# MCU.net
KiCad netlist of a schematic drawn in Altium Designer
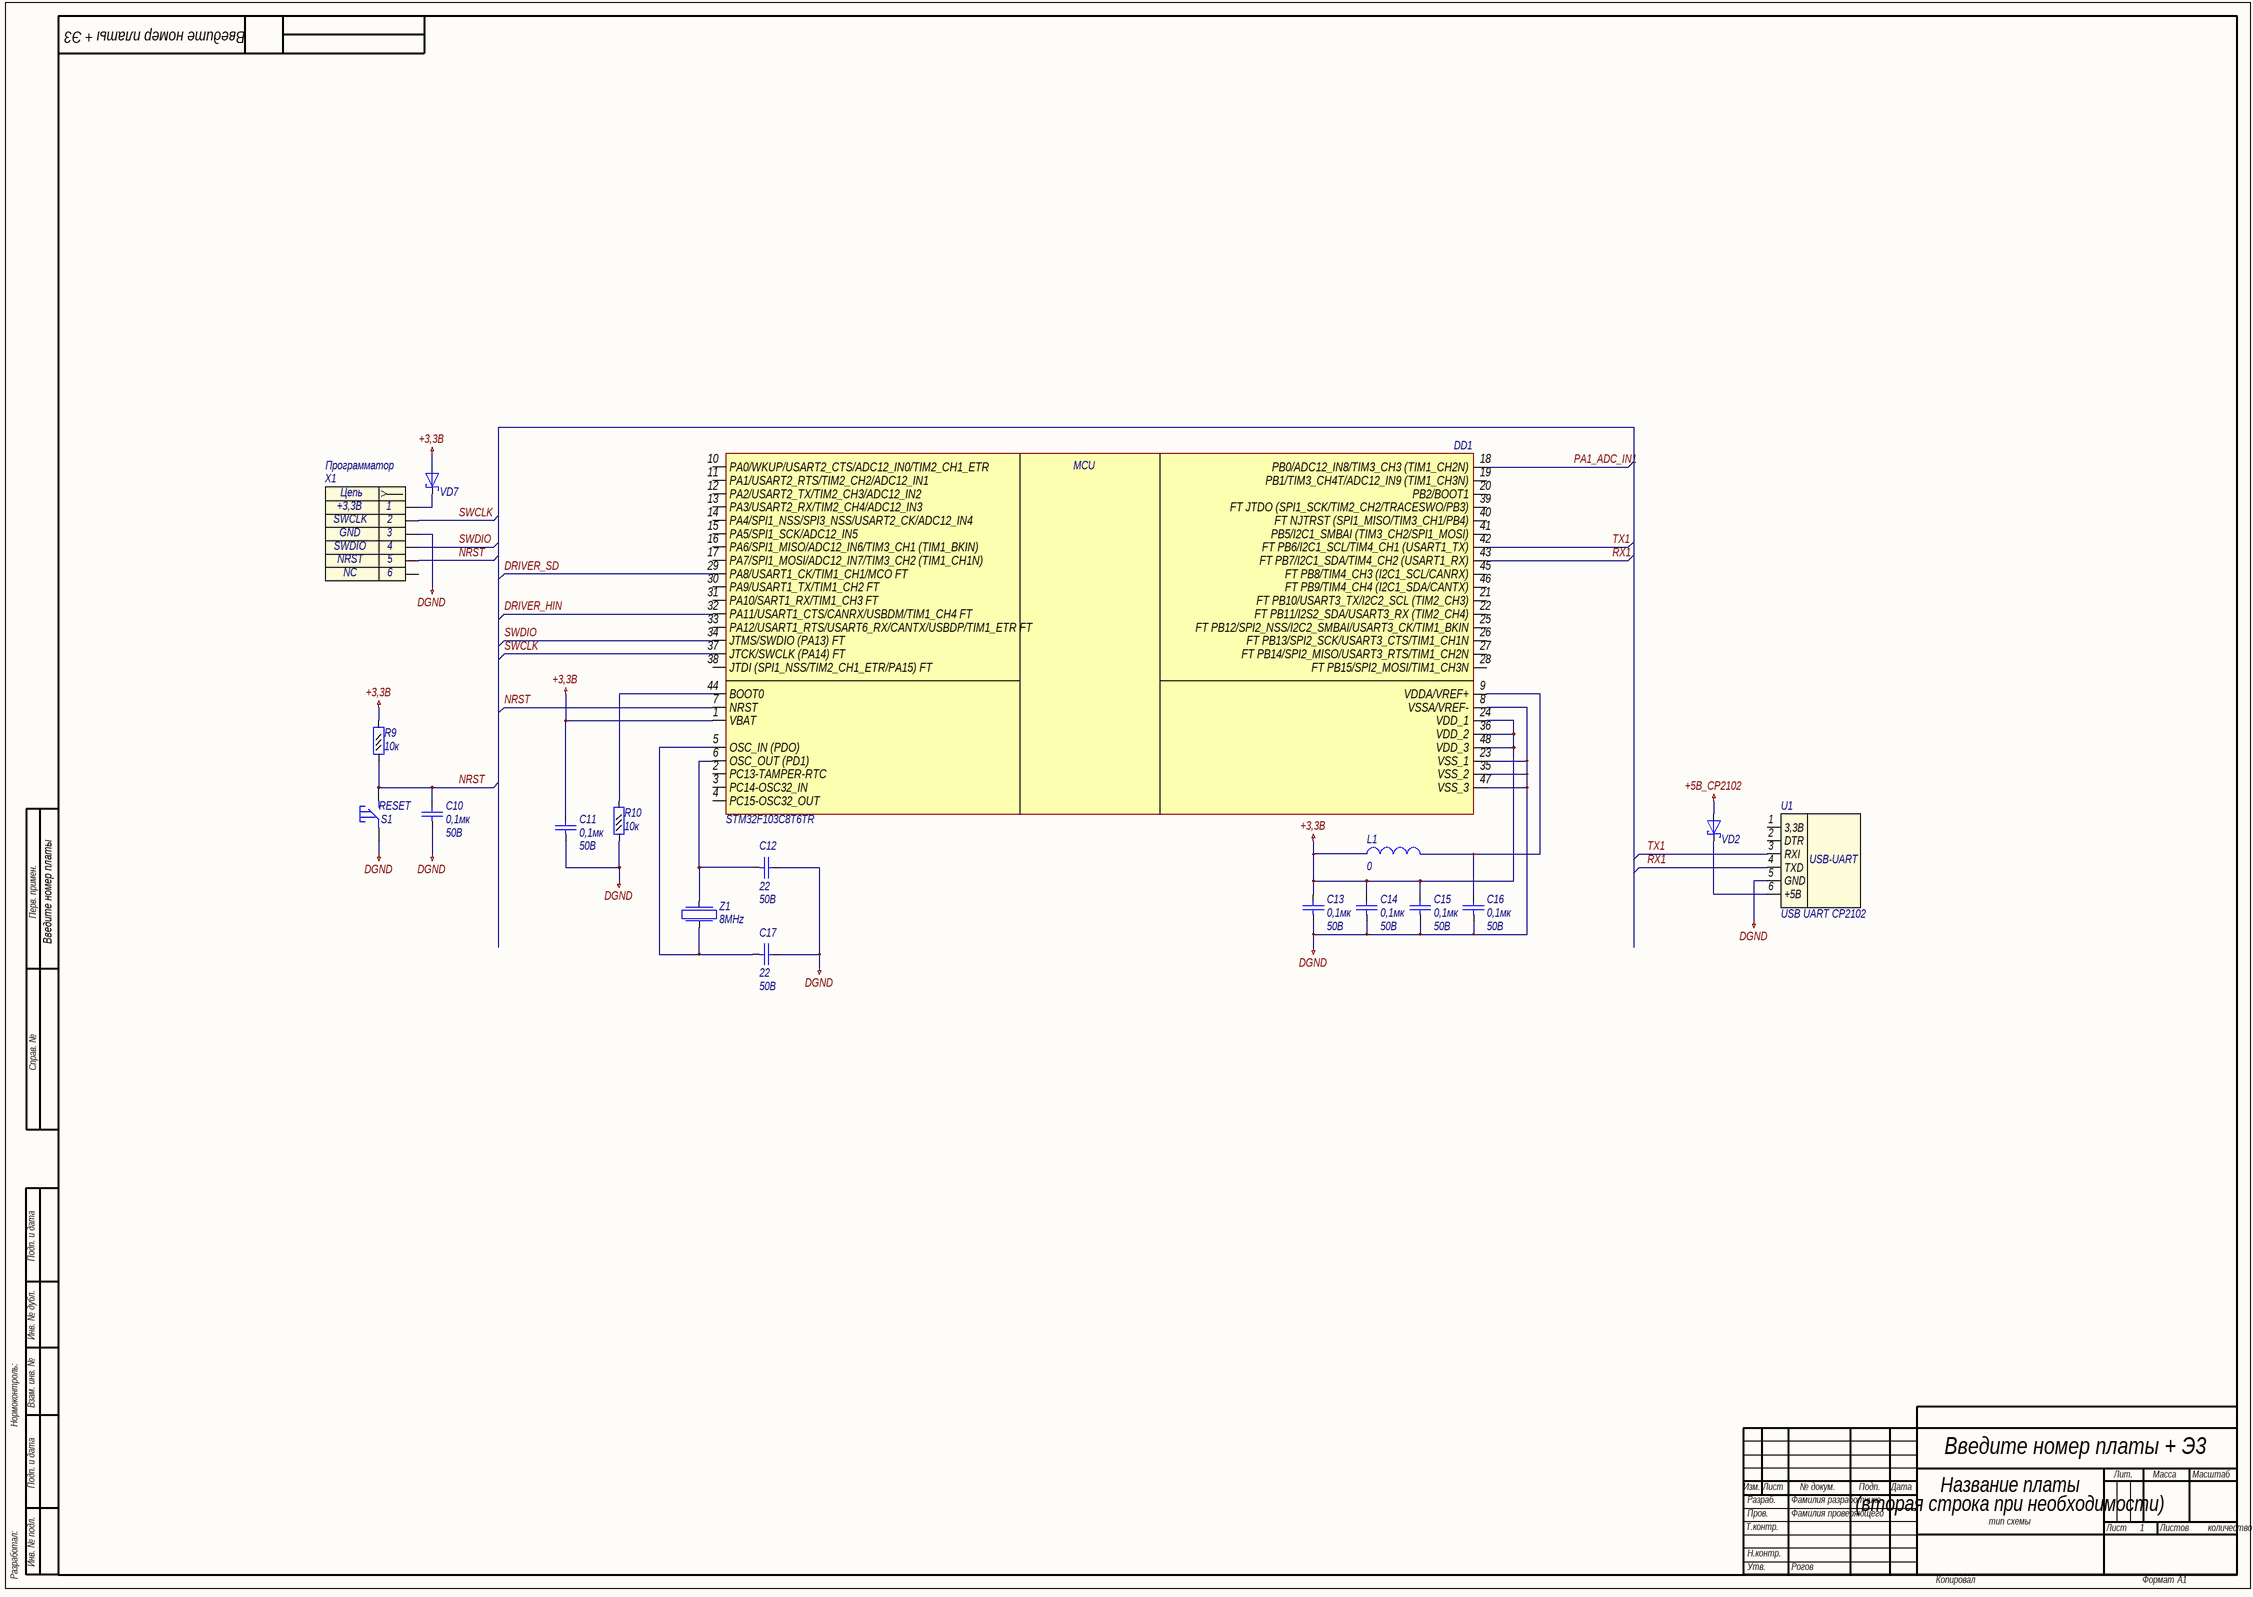
[diagram p0: MCU.SchDoc]

(export (version "E")
  (design (tool "Eeschema 10.0.6"))
  (components
    (comp (ref "C10")
      (value "0,1мк")
      (footprint "C0603")
      (description "Конденсатор")
      (fields
        (field (name "VOLTAGE") "50B")
        (field (name "PART NUMBER") "GRM188R71H104KA93D")
        (field (name "Comment") "Capacitor")
      )
      (libsource (lib "MOP44") (part "Capacitor"))
    )
    (comp (ref "C11")
      (value "0,1мк")
      (footprint "C0603")
      (description "Конденсатор")
      (fields
        (field (name "VOLTAGE") "50B")
        (field (name "PART NUMBER") "GRM188R71H104KA93D")
        (field (name "Comment") "Capacitor")
      )
      (libsource (lib "MOP44") (part "Capacitor"))
    )
    (comp (ref "C12")
      (value "22")
      (footprint "C0603")
      (description "Конденсатор")
      (fields
        (field (name "VOLTAGE") "50B")
        (field (name "PART NUMBER") "CC0603JRNPO9BN220")
        (field (name "Comment") "Capacitor")
      )
      (libsource (lib "MOP44") (part "Capacitor"))
    )
    (comp (ref "C13")
      (value "0,1мк")
      (footprint "C0603")
      (description "Конденсатор")
      (fields
        (field (name "VOLTAGE") "50B")
        (field (name "PART NUMBER") "GRM188R71H104KA93D")
        (field (name "Comment") "Capacitor")
      )
      (libsource (lib "MOP44") (part "Capacitor"))
    )
    (comp (ref "C14")
      (value "0,1мк")
      (footprint "C0603")
      (description "Конденсатор")
      (fields
        (field (name "VOLTAGE") "50B")
        (field (name "PART NUMBER") "GRM188R71H104KA93D")
        (field (name "Comment") "Capacitor")
      )
      (libsource (lib "MOP44") (part "Capacitor"))
    )
    (comp (ref "C15")
      (value "0,1мк")
      (footprint "C0603")
      (description "Конденсатор")
      (fields
        (field (name "VOLTAGE") "50B")
        (field (name "PART NUMBER") "GRM188R71H104KA93D")
        (field (name "Comment") "Capacitor")
      )
      (libsource (lib "MOP44") (part "Capacitor"))
    )
    (comp (ref "C16")
      (value "0,1мк")
      (footprint "C0603")
      (description "Конденсатор")
      (fields
        (field (name "VOLTAGE") "50B")
        (field (name "PART NUMBER") "GRM188R71H104KA93D")
        (field (name "Comment") "Capacitor")
      )
      (libsource (lib "MOP44") (part "Capacitor"))
    )
    (comp (ref "C17")
      (value "22")
      (footprint "C0603")
      (description "Конденсатор")
      (fields
        (field (name "VOLTAGE") "50B")
        (field (name "PART NUMBER") "CC0603JRNPO9BN220")
        (field (name "Comment") "Capacitor")
      )
      (libsource (lib "MOP44") (part "Capacitor"))
    )
    (comp (ref "DD1")
      (value "STM32F103C8T6TR")
      (footprint "LQFP48")
      (fields (field (name "PART NUMBER") "STM32F103C8T6TR"))
      (libsource (lib "MOP44") (part "STM32F103C8T6TR"))
    )
    (comp (ref "L1")
      (value "0")
      (footprint "L0603")
      (description "EMI Suppression Filter")
      (fields (field (name "PART NUMBER") "BLM18PG181SN1D") (field (name "Comment") "Inductor"))
      (libsource (lib "MOP44") (part "Inductor"))
    )
    (comp (ref "R9")
      (value "10к")
      (footprint "R0603")
      (description "Резистор")
      (fields (field (name "PART NUMBER") "RC0603FR-0710KL") (field (name "POWER") "0,062Вт"))
      (libsource (lib "MOP44") (part "Resistor_0,062Вт"))
    )
    (comp (ref "R10")
      (value "10к")
      (footprint "R0603")
      (description "Резистор")
      (fields (field (name "PART NUMBER") "RC0603FR-0710KL") (field (name "POWER") "0,062Вт"))
      (libsource (lib "MOP44") (part "Resistor_0,062Вт"))
    )
    (comp (ref "S1")
      (value "RESET")
      (footprint "Button_SMD")
      (description "Кнопка")
      (libsource (lib "MOP44") (part "Button"))
    )
    (comp (ref "U1")
      (value "USB UART")
      (footprint "USB UART CP2102")
      (description "USB UART module cp2102")
      (fields (field (name "PART NAME") "USB UART CP2102"))
      (libsource (lib "MOP44") (part "USB UART"))
    )
    (comp (ref "VD2")
      (value "DiodeSchottky")
      (footprint "SOD-523")
      (description "Диод Шоттки")
      (fields (field (name "PART NUMBER") "PMEG2010AEB.115"))
      (libsource (lib "MOP44") (part "DiodeSchottky"))
    )
    (comp (ref "VD7")
      (value "DiodeSchottky")
      (footprint "SOD-523")
      (description "Диод Шоттки")
      (fields (field (name "PART NUMBER") "PMEG2010AEB.115"))
      (libsource (lib "MOP44") (part "DiodeSchottky"))
    )
    (comp (ref "X1")
      (value "Программатор")
      (footprint "PLS2-6")
      (description "Разъем - 6 конт. розетка")
      (libsource (lib "MOP44") (part "Header_6_sct"))
    )
    (comp (ref "Z1")
      (value "Crystal")
      (footprint "HC-49S")
      (description "Кварцевый резонатор")
      (fields (field (name "FREQUENCE") "8MHz") (field (name "PART NUMBER") "8.000MHzHC-49US"))
      (libsource (lib "MOP44") (part "Crystal"))
    )
  )
  (nets
    (net (code "1") (name "+3,3В") (class "Default")
      (node (ref "C11") (pin "2") (pinfunction "2_2") (pintype "passive"))
      (node (ref "C13") (pin "2") (pinfunction "2_2") (pintype "passive"))
      (node (ref "C14") (pin "2") (pinfunction "2_2") (pintype "passive"))
      (node (ref "C15") (pin "2") (pinfunction "2_2") (pintype "passive"))
      (node (ref "DD1") (pin "1") (pinfunction "VBAT_1") (pintype "passive"))
      (node (ref "DD1") (pin "24") (pinfunction "VDD_1_24") (pintype "passive"))
      (node (ref "DD1") (pin "36") (pinfunction "VDD_2_36") (pintype "passive"))
      (node (ref "DD1") (pin "48") (pinfunction "VDD_3_48") (pintype "passive"))
      (node (ref "L1") (pin "1") (pinfunction "1_1") (pintype "passive"))
      (node (ref "R9") (pin "2") (pinfunction "2_2") (pintype "passive"))
      (node (ref "VD7") (pin "2") (pinfunction "A_2") (pintype "passive"))
    )
    (net (code "2") (name "+5B_CP2102") (class "Default")
      (node (ref "VD2") (pin "2") (pinfunction "A_2") (pintype "passive"))
    )
    (net (code "3") (name "/DRIVER_HIN") (class "Default")
      (node (ref "DD1") (pin "32") (pinfunction "PA11/USART1_CTS/CANRX/USBDM/TIM1_CH4_FT_32") (pintype "passive"))
    )
    (net (code "4") (name "/DRIVER_SD") (class "Default")
      (node (ref "DD1") (pin "29") (pinfunction "PA8/USART1_CK/TIM1_CH1/MCO_FT_29") (pintype "passive"))
    )
    (net (code "5") (name "/NRST") (class "Default")
      (node (ref "C10") (pin "2") (pinfunction "2_2") (pintype "passive"))
      (node (ref "DD1") (pin "7") (pinfunction "NRST_7") (pintype "passive"))
      (node (ref "R9") (pin "1") (pinfunction "1_1") (pintype "passive"))
      (node (ref "S1") (pin "4") (pinfunction "4_4") (pintype "passive"))
      (node (ref "X1") (pin "5") (pinfunction "5_5") (pintype "passive"))
    )
    (net (code "6") (name "/PA1_ADC_IN1") (class "Default")
      (node (ref "DD1") (pin "18") (pinfunction "PB0/ADC12_IN8/TIM3_CH3_(TIM1_CH2N)_18") (pintype "passive"))
    )
    (net (code "7") (name "/RX1") (class "Default")
      (node (ref "DD1") (pin "43") (pinfunction "FT_PB7/I2C1_SDA/TIM4_CH2_(USART1_RX)_43") (pintype "passive"))
      (node (ref "U1") (pin "4") (pinfunction "TXD_4") (pintype "power_in"))
    )
    (net (code "8") (name "/SWCLK") (class "Default")
      (node (ref "DD1") (pin "37") (pinfunction "JTCK/SWCLK_(PA14)_FT_37") (pintype "passive"))
      (node (ref "X1") (pin "2") (pinfunction "2_2") (pintype "passive"))
    )
    (net (code "9") (name "/SWDIO") (class "Default")
      (node (ref "DD1") (pin "34") (pinfunction "JTMS/SWDIO_(PA13)_FT_34") (pintype "passive"))
      (node (ref "X1") (pin "4") (pinfunction "4_4") (pintype "passive"))
    )
    (net (code "10") (name "/TX1") (class "Default")
      (node (ref "DD1") (pin "42") (pinfunction "FT_PB6/I2C1_SCL/TIM4_CH1_(USART1_TX)_42") (pintype "passive"))
      (node (ref "U1") (pin "3") (pinfunction "RXI_3") (pintype "power_in"))
    )
    (net (code "11") (name "DGND") (class "Default")
      (node (ref "C10") (pin "1") (pinfunction "1_1") (pintype "passive"))
      (node (ref "C11") (pin "1") (pinfunction "1_1") (pintype "passive"))
      (node (ref "C12") (pin "2") (pinfunction "2_2") (pintype "passive"))
      (node (ref "C13") (pin "1") (pinfunction "1_1") (pintype "passive"))
      (node (ref "C14") (pin "1") (pinfunction "1_1") (pintype "passive"))
      (node (ref "C15") (pin "1") (pinfunction "1_1") (pintype "passive"))
      (node (ref "C16") (pin "1") (pinfunction "1_1") (pintype "passive"))
      (node (ref "C17") (pin "2") (pinfunction "2_2") (pintype "passive"))
      (node (ref "DD1") (pin "23") (pinfunction "VSS_1_23") (pintype "passive"))
      (node (ref "DD1") (pin "35") (pinfunction "VSS_2_35") (pintype "passive"))
      (node (ref "DD1") (pin "47") (pinfunction "VSS_3_47") (pintype "passive"))
      (node (ref "DD1") (pin "8") (pinfunction "VSSA/VREF-_8") (pintype "passive"))
      (node (ref "R10") (pin "1") (pinfunction "1_1") (pintype "passive"))
      (node (ref "S1") (pin "1") (pinfunction "1_1") (pintype "passive"))
      (node (ref "U1") (pin "5") (pinfunction "GND_5") (pintype "power_in"))
      (node (ref "X1") (pin "3") (pinfunction "3_3") (pintype "passive"))
    )
    (net (code "12") (name "Net-(DD1-BOOT0)") (class "Default")
      (node (ref "DD1") (pin "44") (pinfunction "BOOT0_44") (pintype "passive"))
      (node (ref "R10") (pin "2") (pinfunction "2_2") (pintype "passive"))
    )
    (net (code "13") (name "Net-(DD1-OSC_IN_(PDO))") (class "Default")
      (node (ref "C17") (pin "1") (pinfunction "1_1") (pintype "passive"))
      (node (ref "DD1") (pin "5") (pinfunction "OSC_IN_(PDO)_5") (pintype "passive"))
      (node (ref "Z1") (pin "1") (pinfunction "1_1") (pintype "passive"))
    )
    (net (code "14") (name "Net-(DD1-OSC_OUT_(PD1))") (class "Default")
      (node (ref "C12") (pin "1") (pinfunction "1_1") (pintype "passive"))
      (node (ref "DD1") (pin "6") (pinfunction "OSC_OUT_(PD1)_6") (pintype "passive"))
      (node (ref "Z1") (pin "2") (pinfunction "2_2") (pintype "passive"))
    )
    (net (code "15") (name "Net-(DD1-VDDA{slash}VREF+)") (class "Default")
      (node (ref "C16") (pin "2") (pinfunction "2_2") (pintype "passive"))
      (node (ref "DD1") (pin "9") (pinfunction "VDDA/VREF+_9") (pintype "passive"))
      (node (ref "L1") (pin "2") (pinfunction "2_2") (pintype "passive"))
    )
    (net (code "16") (name "Net-(U1-+5B)") (class "Default")
      (node (ref "U1") (pin "6") (pinfunction "+5B_6") (pintype "power_in"))
      (node (ref "VD2") (pin "1") (pinfunction "K_1") (pintype "passive"))
    )
    (net (code "17") (name "Net-(VD7-K)") (class "Default")
      (node (ref "VD7") (pin "1") (pinfunction "K_1") (pintype "passive"))
      (node (ref "X1") (pin "1") (pinfunction "1_1") (pintype "passive"))
    )
    (net (code "18") (name "unconnected-(DD1-FT_JTDO_(SPI1_SCK{slash}TIM2_CH2{slash}TRACESWO{slash}PB3)-Pad39)") (class "Default")
      (node (ref "DD1") (pin "39") (pinfunction "FT_JTDO_(SPI1_SCK/TIM2_CH2/TRACESWO/PB3)_39") (pintype "passive"))
    )
    (net (code "19") (name "unconnected-(DD1-FT_NJTRST_(SPI1_MISO{slash}TIM3_CH1{slash}PB4)-Pad40)") (class "Default")
      (node (ref "DD1") (pin "40") (pinfunction "FT_NJTRST_(SPI1_MISO/TIM3_CH1/PB4)_40") (pintype "passive"))
    )
    (net (code "20") (name "unconnected-(DD1-FT_PB8{slash}TIM4_CH3_(I2C1_SCL{slash}CANRX)-Pad45)") (class "Default")
      (node (ref "DD1") (pin "45") (pinfunction "FT_PB8/TIM4_CH3_(I2C1_SCL/CANRX)_45") (pintype "passive"))
    )
    (net (code "21") (name "unconnected-(DD1-FT_PB9{slash}TIM4_CH4_(I2C1_SDA{slash}CANTX)-Pad46)") (class "Default")
      (node (ref "DD1") (pin "46") (pinfunction "FT_PB9/TIM4_CH4_(I2C1_SDA/CANTX)_46") (pintype "passive"))
    )
    (net (code "22") (name "unconnected-(DD1-FT_PB10{slash}USART3_TX{slash}I2C2_SCL_(TIM2_CH3)-Pad21)") (class "Default")
      (node (ref "DD1") (pin "21") (pinfunction "FT_PB10/USART3_TX/I2C2_SCL_(TIM2_CH3)_21") (pintype "passive"))
    )
    (net (code "23") (name "unconnected-(DD1-FT_PB11{slash}I2S2_SDA{slash}USART3_RX_(TIM2_CH4)-Pad22)") (class "Default")
      (node (ref "DD1") (pin "22") (pinfunction "FT_PB11/I2S2_SDA/USART3_RX_(TIM2_CH4)_22") (pintype "passive"))
    )
    (net (code "24") (name "unconnected-(DD1-FT_PB12{slash}SPI2_NSS{slash}I2C2_SMBAI{slash}USART3_CK{slash}TIM1_BKIN-Pad25)") (class "Default")
      (node (ref "DD1") (pin "25") (pinfunction "FT_PB12/SPI2_NSS/I2C2_SMBAI/USART3_CK/TIM1_BKIN_25") (pintype "passive"))
    )
    (net (code "25") (name "unconnected-(DD1-FT_PB13{slash}SPI2_SCK{slash}USART3_CTS{slash}TIM1_CH1N-Pad26)") (class "Default")
      (node (ref "DD1") (pin "26") (pinfunction "FT_PB13/SPI2_SCK/USART3_CTS/TIM1_CH1N_26") (pintype "passive"))
    )
    (net (code "26") (name "unconnected-(DD1-FT_PB14{slash}SPI2_MISO{slash}USART3_RTS{slash}TIM1_CH2N-Pad27)") (class "Default")
      (node (ref "DD1") (pin "27") (pinfunction "FT_PB14/SPI2_MISO/USART3_RTS/TIM1_CH2N_27") (pintype "passive"))
    )
    (net (code "27") (name "unconnected-(DD1-FT_PB15{slash}SPI2_MOSI{slash}TIM1_CH3N-Pad28)") (class "Default")
      (node (ref "DD1") (pin "28") (pinfunction "FT_PB15/SPI2_MOSI/TIM1_CH3N_28") (pintype "passive"))
    )
    (net (code "28") (name "unconnected-(DD1-JTDI_(SPI1_NSS{slash}TIM2_CH1_ETR{slash}PA15)_FT-Pad38)") (class "Default")
      (node (ref "DD1") (pin "38") (pinfunction "JTDI_(SPI1_NSS/TIM2_CH1_ETR/PA15)_FT_38") (pintype "passive"))
    )
    (net (code "29") (name "unconnected-(DD1-PA0{slash}WKUP{slash}USART2_CTS{slash}ADC12_IN0{slash}TIM2_CH1_ETR-Pad10)") (class "Default")
      (node (ref "DD1") (pin "10") (pinfunction "PA0/WKUP/USART2_CTS/ADC12_IN0/TIM2_CH1_ETR_10") (pintype "passive"))
    )
    (net (code "30") (name "unconnected-(DD1-PA1{slash}USART2_RTS{slash}TIM2_CH2{slash}ADC12_IN1-Pad11)") (class "Default")
      (node (ref "DD1") (pin "11") (pinfunction "PA1/USART2_RTS/TIM2_CH2/ADC12_IN1_11") (pintype "passive"))
    )
    (net (code "31") (name "unconnected-(DD1-PA2{slash}USART2_TX{slash}TIM2_CH3{slash}ADC12_IN2-Pad12)") (class "Default")
      (node (ref "DD1") (pin "12") (pinfunction "PA2/USART2_TX/TIM2_CH3/ADC12_IN2_12") (pintype "passive"))
    )
    (net (code "32") (name "unconnected-(DD1-PA3{slash}USART2_RX{slash}TIM2_CH4{slash}ADC12_IN3-Pad13)") (class "Default")
      (node (ref "DD1") (pin "13") (pinfunction "PA3/USART2_RX/TIM2_CH4/ADC12_IN3_13") (pintype "passive"))
    )
    (net (code "33") (name "unconnected-(DD1-PA4{slash}SPI1_NSS{slash}SPI3_NSS{slash}USART2_CK{slash}ADC12_IN4-Pad14)") (class "Default")
      (node (ref "DD1") (pin "14") (pinfunction "PA4/SPI1_NSS/SPI3_NSS/USART2_CK/ADC12_IN4_14") (pintype "passive"))
    )
    (net (code "34") (name "unconnected-(DD1-PA5{slash}SPI1_SCK{slash}ADC12_IN5-Pad15)") (class "Default")
      (node (ref "DD1") (pin "15") (pinfunction "PA5/SPI1_SCK/ADC12_IN5_15") (pintype "passive"))
    )
    (net (code "35") (name "unconnected-(DD1-PA6{slash}SPI1_MISO{slash}ADC12_IN6{slash}TIM3_CH1_(TIM1_BKIN)-Pad16)") (class "Default")
      (node (ref "DD1") (pin "16") (pinfunction "PA6/SPI1_MISO/ADC12_IN6/TIM3_CH1_(TIM1_BKIN)_16") (pintype "passive"))
    )
    (net (code "36") (name "unconnected-(DD1-PA7{slash}SPI1_MOSI{slash}ADC12_IN7{slash}TIM3_CH2_(TIM1_CH1N)-Pad17)") (class "Default")
      (node (ref "DD1") (pin "17") (pinfunction "PA7/SPI1_MOSI/ADC12_IN7/TIM3_CH2_(TIM1_CH1N)_17") (pintype "passive"))
    )
    (net (code "37") (name "unconnected-(DD1-PA9{slash}USART1_TX{slash}TIM1_CH2_FT-Pad30)") (class "Default")
      (node (ref "DD1") (pin "30") (pinfunction "PA9/USART1_TX/TIM1_CH2_FT_30") (pintype "passive"))
    )
    (net (code "38") (name "unconnected-(DD1-PA10{slash}SART1_RX{slash}TIM1_CH3_FT-Pad31)") (class "Default")
      (node (ref "DD1") (pin "31") (pinfunction "PA10/SART1_RX/TIM1_CH3_FT_31") (pintype "passive"))
    )
    (net (code "39") (name "unconnected-(DD1-PA12{slash}USART1_RTS{slash}USART6_RX{slash}CANTX{slash}USBDP{slash}TIM1_ETR_FT-Pad33)") (class "Default")
      (node (ref "DD1") (pin "33") (pinfunction "PA12/USART1_RTS/USART6_RX/CANTX/USBDP/TIM1_ETR_FT_33") (pintype "passive"))
    )
    (net (code "40") (name "unconnected-(DD1-PB1{slash}TIM3_CH4T{slash}ADC12_IN9_(TIM1_CH3N)-Pad19)") (class "Default")
      (node (ref "DD1") (pin "19") (pinfunction "PB1/TIM3_CH4T/ADC12_IN9_(TIM1_CH3N)_19") (pintype "passive"))
    )
    (net (code "41") (name "unconnected-(DD1-PB2{slash}BOOT1-Pad20)") (class "Default")
      (node (ref "DD1") (pin "20") (pinfunction "PB2/BOOT1_20") (pintype "passive"))
    )
    (net (code "42") (name "unconnected-(DD1-PB5{slash}I2C1_SMBAI_(TIM3_CH2{slash}SPI1_MOSI)-Pad41)") (class "Default")
      (node (ref "DD1") (pin "41") (pinfunction "PB5/I2C1_SMBAI_(TIM3_CH2/SPI1_MOSI)_41") (pintype "passive"))
    )
    (net (code "43") (name "unconnected-(DD1-PC13-TAMPER-RTC-Pad2)") (class "Default")
      (node (ref "DD1") (pin "2") (pinfunction "PC13-TAMPER-RTC_2") (pintype "passive"))
    )
    (net (code "44") (name "unconnected-(DD1-PC14-OSC32_IN-Pad3)") (class "Default")
      (node (ref "DD1") (pin "3") (pinfunction "PC14-OSC32_IN_3") (pintype "passive"))
    )
    (net (code "45") (name "unconnected-(DD1-PC15-OSC32_OUT-Pad4)") (class "Default")
      (node (ref "DD1") (pin "4") (pinfunction "PC15-OSC32_OUT_4") (pintype "passive"))
    )
    (net (code "46") (name "unconnected-(U1-3,3B-Pad1)") (class "Default")
      (node (ref "U1") (pin "1") (pinfunction "3,3B_1") (pintype "power_in"))
    )
    (net (code "47") (name "unconnected-(U1-DTR-Pad2)") (class "Default")
      (node (ref "U1") (pin "2") (pinfunction "DTR_2") (pintype "power_in"))
    )
    (net (code "48") (name "unconnected-(X1-Pad6)") (class "Default")
      (node (ref "X1") (pin "6") (pinfunction "6_6") (pintype "passive"))
    )
  )
)
